# SCH_Lab-bench-Power-Supply_2025-04-24.net
KiCad netlist of a schematic drawn in EasyEDA
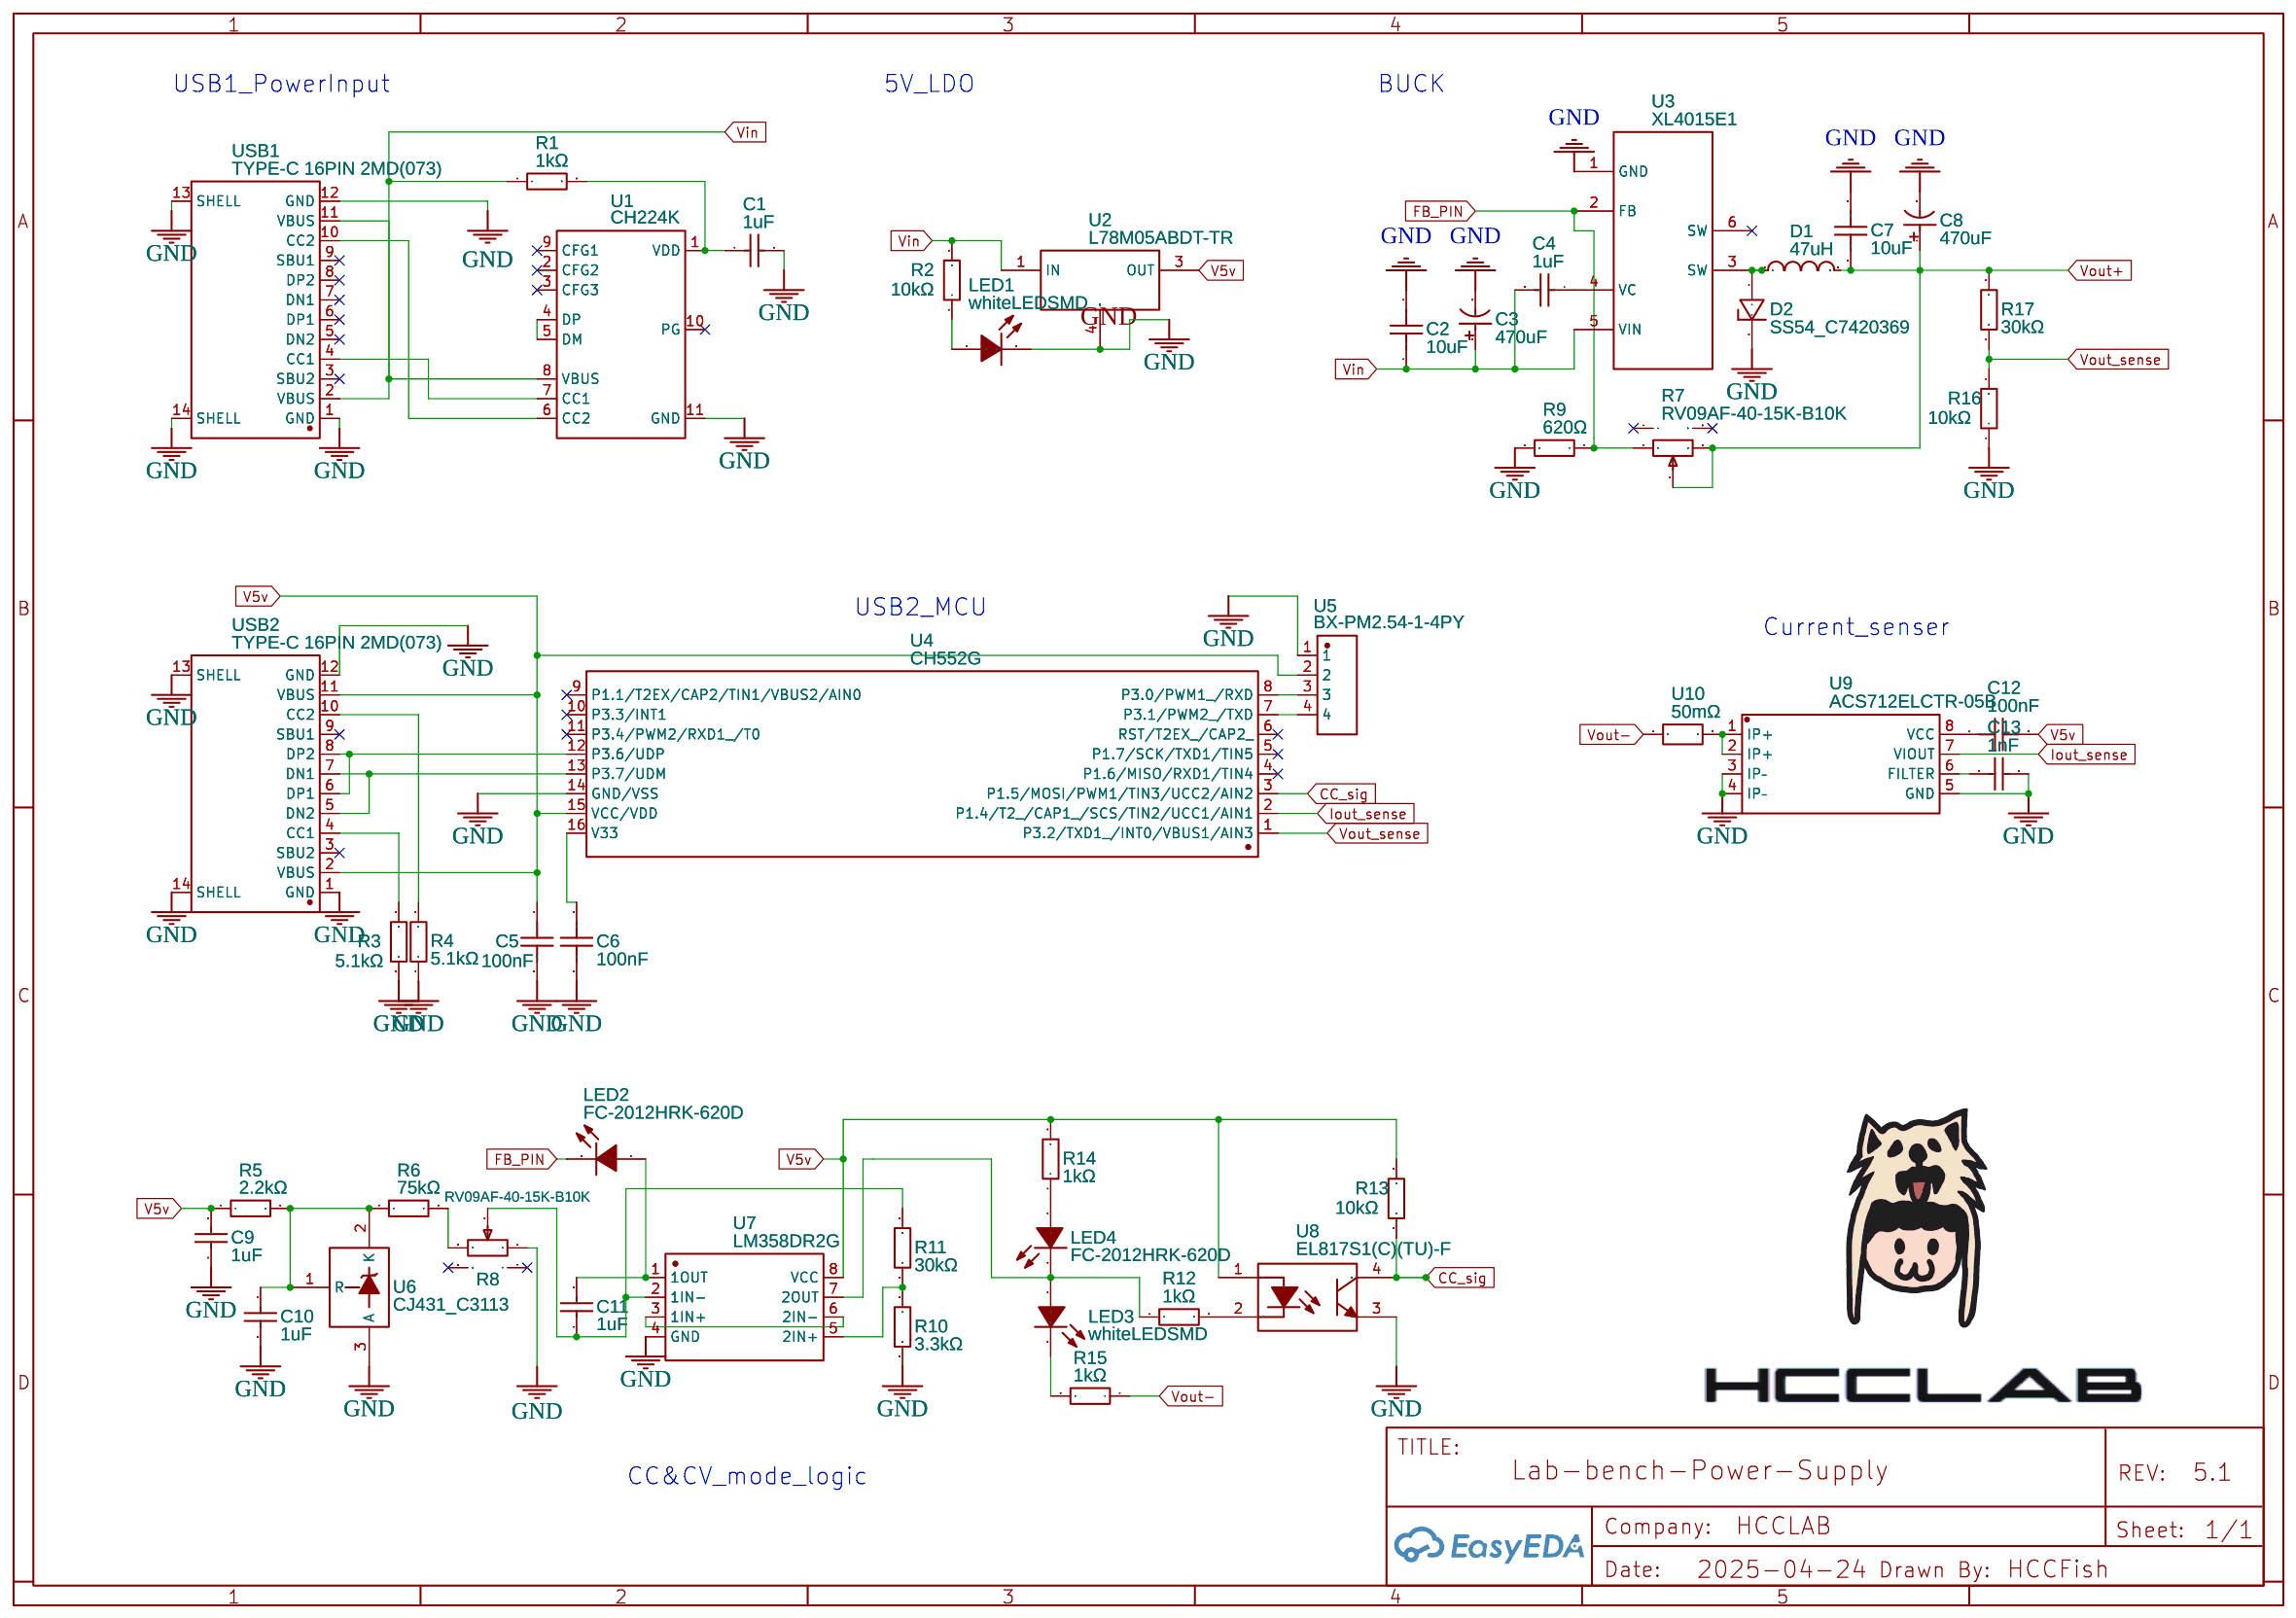
[diagram p0: schematic sheet]

(export (version "E")
  (design (tool "Eeschema 10.0.6"))
  (components
    (comp (ref "C1")
      (value "1uF")
      (fields
        (field (name "Manufacturer Part") "CL21B105KBFNNNE")
        (field (name "Manufacturer") "SAMSUNG(三星)")
      )
      (libsource (lib "") (part "CL21B105KBFNNNE_2"))
    )
    (comp (ref "C2")
      (value "10uF")
      (fields
        (field (name "Manufacturer Part") "CL21A106KAYNNNE")
        (field (name "Manufacturer") "SAMSUNG(三星)")
      )
      (libsource (lib "") (part "CL21A106KAYNNNE"))
    )
    (comp (ref "C3")
      (value "470uF")
      (fields
        (field (name "Manufacturer Part") "KM477M025F12RR0VH2FP0")
        (field (name "Manufacturer") "CX(承兴)")
      )
      (libsource (lib "") (part "470uF 25V 8*12"))
    )
    (comp (ref "C4")
      (value "1uF")
      (fields
        (field (name "Manufacturer Part") "CL21B105KBFNNNE")
        (field (name "Manufacturer") "SAMSUNG(三星)")
      )
      (libsource (lib "") (part "CL21B105KBFNNNE"))
    )
    (comp (ref "C5")
      (value "100nF")
      (fields
        (field (name "Manufacturer Part") "CC0805KRX7R9BB104")
        (field (name "Manufacturer") "YAGEO(国巨)")
      )
      (libsource (lib "") (part "CC0805KRX7R9BB104_2"))
    )
    (comp (ref "C6")
      (value "100nF")
      (fields
        (field (name "Manufacturer Part") "CC0805KRX7R9BB104")
        (field (name "Manufacturer") "YAGEO(国巨)")
      )
      (libsource (lib "") (part "CC0805KRX7R9BB104"))
    )
    (comp (ref "C7")
      (value "10uF")
      (fields
        (field (name "Manufacturer Part") "CL21A106KAYNNNE")
        (field (name "Manufacturer") "SAMSUNG(三星)")
      )
      (libsource (lib "") (part "CL21A106KAYNNNE"))
    )
    (comp (ref "C8")
      (value "470uF")
      (fields
        (field (name "Manufacturer Part") "KM477M025F12RR0VH2FP0")
        (field (name "Manufacturer") "CX(承兴)")
      )
      (libsource (lib "") (part "470uF 25V 8*12"))
    )
    (comp (ref "C9")
      (value "1uF")
      (fields
        (field (name "Manufacturer Part") "CL21B105KBFNNNE")
        (field (name "Manufacturer") "SAMSUNG(三星)")
      )
      (libsource (lib "") (part "CL21B105KBFNNNE_1"))
    )
    (comp (ref "C10")
      (value "1uF")
      (fields
        (field (name "Manufacturer Part") "CL21B105KBFNNNE")
        (field (name "Manufacturer") "SAMSUNG(三星)")
      )
      (libsource (lib "") (part "CL21B105KBFNNNE_1"))
    )
    (comp (ref "C11")
      (value "1uF")
      (fields
        (field (name "Manufacturer Part") "CL21B105KBFNNNE")
        (field (name "Manufacturer") "SAMSUNG(三星)")
      )
      (libsource (lib "") (part "CL21B105KBFNNNE_3"))
    )
    (comp (ref "C12")
      (value "100nF")
      (fields
        (field (name "Manufacturer Part") "CC0805KRX7R9BB104")
        (field (name "Manufacturer") "YAGEO(国巨)")
      )
      (libsource (lib "") (part "CC0805KRX7R9BB104_1"))
    )
    (comp (ref "C13")
      (value "1nF")
      (fields
        (field (name "Manufacturer Part") "CL21B102KBCNNNC")
        (field (name "Manufacturer") "SAMSUNG(三星)")
      )
      (libsource (lib "") (part "CL21B102KBCNNNC"))
    )
    (comp (ref "D1")
      (value "47uH")
      (fields (field (name "Manufacturer Part") "SRP1265A-470M") (field (name "Manufacturer") "BOURNS"))
      (libsource (lib "") (part "SRP1265A-470M"))
    )
    (comp (ref "D2")
      (value "SS54_C7420369")
      (fields (field (name "Manufacturer Part") "SS54") (field (name "Manufacturer") "宏迦橙"))
      (libsource (lib "") (part "SS54_C7420369"))
    )
    (comp (ref "LED1")
      (value "whiteLEDSMD")
      (fields (field (name "Manufacturer Part") "KT-0805W") (field (name "Manufacturer") "KENTO"))
      (libsource (lib "") (part "whiteLEDSMD"))
    )
    (comp (ref "LED2")
      (value "FC-2012HRK-620D")
      (fields (field (name "Manufacturer Part") "NCD0805R1") (field (name "Manufacturer") "国星光电"))
      (libsource (lib "") (part "FC-2012HRK-620D"))
    )
    (comp (ref "LED3")
      (value "whiteLEDSMD")
      (fields (field (name "Manufacturer Part") "KT-0805W") (field (name "Manufacturer") "KENTO"))
      (libsource (lib "") (part "whiteLEDSMD_1"))
    )
    (comp (ref "LED4")
      (value "FC-2012HRK-620D")
      (fields (field (name "Manufacturer Part") "NCD0805R1") (field (name "Manufacturer") "国星光电"))
      (libsource (lib "") (part "FC-2012HRK-620D_1"))
    )
    (comp (ref "R1")
      (value "1kΩ")
      (fields
        (field (name "Manufacturer Part") "0805W8F1001T5E")
        (field (name "Manufacturer") "UNI-ROYAL(厚声)")
      )
      (libsource (lib "") (part "0805W8F1001T5E"))
    )
    (comp (ref "R2")
      (value "10kΩ")
      (fields
        (field (name "Manufacturer Part") "0805W8F1002T5E")
        (field (name "Manufacturer") "UNI-ROYAL(厚声)")
      )
      (libsource (lib "") (part "0805W8F1002T5E"))
    )
    (comp (ref "R3")
      (value "5.1kΩ")
      (fields
        (field (name "Manufacturer Part") "0805W8F5101T5E")
        (field (name "Manufacturer") "UNI-ROYAL(厚声)")
      )
      (libsource (lib "") (part "0805W8F5101T5E"))
    )
    (comp (ref "R4")
      (value "5.1kΩ")
      (fields
        (field (name "Manufacturer Part") "0805W8F5101T5E")
        (field (name "Manufacturer") "UNI-ROYAL(厚声)")
      )
      (libsource (lib "") (part "0805W8F5101T5E"))
    )
    (comp (ref "R5")
      (value "2.2kΩ")
      (fields
        (field (name "Manufacturer Part") "0805W8F2201T5E")
        (field (name "Manufacturer") "UNI-ROYAL(厚声)")
      )
      (libsource (lib "") (part "0805W8F2201T5E"))
    )
    (comp (ref "R6")
      (value "75kΩ")
      (fields
        (field (name "Manufacturer Part") "0805W8F7502T5E")
        (field (name "Manufacturer") "UNI-ROYAL(厚声)")
      )
      (libsource (lib "") (part "0805W8F7502T5E"))
    )
    (comp (ref "R7") (value "RV09AF-40-15K-B10K") (libsource (lib "") (part "RV09AF-40-15K-B10K_1")))
    (comp (ref "R8") (value "RV09AF-40-15K-B10K") (libsource (lib "") (part "RV09AF-40-15K-B10K")))
    (comp (ref "R9")
      (value "620Ω")
      (fields
        (field (name "Manufacturer Part") "0603WAF6200T5E")
        (field (name "Manufacturer") "UNI-ROYAL(厚声)")
      )
      (libsource (lib "") (part "0603WAF6200T5E"))
    )
    (comp (ref "R10")
      (value "3.3kΩ")
      (fields
        (field (name "Manufacturer Part") "0805W8F3301T5E")
        (field (name "Manufacturer") "UNI-ROYAL(厚声)")
      )
      (libsource (lib "") (part "0805W8F3301T5E"))
    )
    (comp (ref "R11")
      (value "30kΩ")
      (fields
        (field (name "Manufacturer Part") "0805W8F3002T5E")
        (field (name "Manufacturer") "UNI-ROYAL(厚声)")
      )
      (libsource (lib "") (part "0805W8F3002T5E"))
    )
    (comp (ref "R12")
      (value "1kΩ")
      (fields
        (field (name "Manufacturer Part") "0805W8F1001T5E")
        (field (name "Manufacturer") "UNI-ROYAL(厚声)")
      )
      (libsource (lib "") (part "0805W8F1001T5E"))
    )
    (comp (ref "R13")
      (value "10kΩ")
      (fields
        (field (name "Manufacturer Part") "0805W8F1002T5E")
        (field (name "Manufacturer") "UNI-ROYAL(厚声)")
      )
      (libsource (lib "") (part "0805W8F1002T5E"))
    )
    (comp (ref "R14")
      (value "1kΩ")
      (fields
        (field (name "Manufacturer Part") "0805W8F1001T5E")
        (field (name "Manufacturer") "UNI-ROYAL(厚声)")
      )
      (libsource (lib "") (part "0805W8F1001T5E_1"))
    )
    (comp (ref "R15")
      (value "1kΩ")
      (fields
        (field (name "Manufacturer Part") "0805W8F1001T5E")
        (field (name "Manufacturer") "UNI-ROYAL(厚声)")
      )
      (libsource (lib "") (part "0805W8F1001T5E_2"))
    )
    (comp (ref "R16")
      (value "10kΩ")
      (fields
        (field (name "Manufacturer Part") "0805W8F1002T5E")
        (field (name "Manufacturer") "UNI-ROYAL(厚声)")
      )
      (libsource (lib "") (part "0805W8F1002T5E"))
    )
    (comp (ref "R17")
      (value "30kΩ")
      (fields
        (field (name "Manufacturer Part") "0805W8F3002T5E")
        (field (name "Manufacturer") "UNI-ROYAL(厚声)")
      )
      (libsource (lib "") (part "0805W8F3002T5E"))
    )
    (comp (ref "U1")
      (value "CH224K")
      (fields (field (name "Manufacturer") "WCH(南京沁恒)"))
      (libsource (lib "") (part "CH224K"))
    )
    (comp (ref "U2")
      (value "L78M05ABDT-TR")
      (fields (field (name "Manufacturer") "ST(意法半导体)"))
      (libsource (lib "") (part "L78M05ABDT-TR"))
    )
    (comp (ref "U3")
      (value "XL4015E1")
      (fields (field (name "Manufacturer") "XLSEMI(芯龙)"))
      (libsource (lib "") (part "XL4015E1"))
    )
    (comp (ref "U4")
      (value "CH552G")
      (fields (field (name "Manufacturer") "WCH(南京沁恒)"))
      (libsource (lib "") (part "CH552G"))
    )
    (comp (ref "U5")
      (value "BX-PM2.54-1-4PY")
      (fields (field (name "Manufacturer") "Bossie(博锡)"))
      (libsource (lib "") (part "BX-PM2.54-1-4PY"))
    )
    (comp (ref "U6")
      (value "CJ431_C3113")
      (fields (field (name "Manufacturer Part") "CJ431") (field (name "Manufacturer") "CJ(江苏长电/长晶)"))
      (libsource (lib "") (part "CJ431_C3113"))
    )
    (comp (ref "U7")
      (value "LM358DR2G")
      (fields (field (name "Manufacturer") "onsemi(安森美)"))
      (libsource (lib "") (part "LM358DR2G"))
    )
    (comp (ref "U8")
      (value "EL817S1(C)(TU)-F")
      (fields (field (name "Manufacturer") "EVERLIGHT(亿光)"))
      (libsource (lib "") (part "EL817S1(C)(TU)-F"))
    )
    (comp (ref "U9")
      (value "ACS712ELCTR-05B")
      (fields (field (name "Manufacturer") "ALLEGRO(美国埃戈罗)"))
      (libsource (lib "") (part "ACS712ELCTR-05B"))
    )
    (comp (ref "U10")
      (value "50mΩ")
      (fields
        (field (name "Manufacturer Part") "HoYLR2512-3W-50mR-1%")
        (field (name "Manufacturer") "Milliohm(毫欧)")
      )
      (libsource (lib "") (part "HOYLR2512-3W-50MR-1%"))
    )
    (comp (ref "USB1")
      (value "TYPE-C 16PIN 2MD(073)")
      (fields (field (name "Manufacturer") "SHOU HAN(首韩)"))
      (libsource (lib "") (part "TYPE-C 16PIN 2MD(073)"))
    )
    (comp (ref "USB2")
      (value "TYPE-C 16PIN 2MD(073)")
      (fields (field (name "Manufacturer") "SHOU HAN(首韩)"))
      (libsource (lib "") (part "TYPE-C 16PIN 2MD(073)"))
    )
  )
  (nets
    (net (code "1") (name "CC_sig") (class "Default")
      (node (ref "R13") (pin "1") (pinfunction "1_1") (pintype "input"))
      (node (ref "U4") (pin "3") (pinfunction "P1.5/MOSI/PWM1/TIN3/UCC2/AIN2_3") (pintype "unspecified"))
      (node (ref "U8") (pin "4") (pinfunction "COL_4") (pintype "unspecified"))
    )
    (net (code "2") (name "FB_PIN") (class "Default")
      (node (ref "LED2") (pin "2") (pinfunction "-_2") (pintype "unspecified"))
      (node (ref "R7") (pin "1") (pinfunction "1_1") (pintype "input"))
      (node (ref "R9") (pin "1") (pinfunction "1_1") (pintype "input"))
      (node (ref "U3") (pin "2") (pinfunction "FB_2") (pintype "unspecified"))
    )
    (net (code "3") (name "GND") (class "Default")
      (node (ref "C1") (pin "2") (pinfunction "2_2") (pintype "input"))
      (node (ref "C10") (pin "2") (pinfunction "2_2") (pintype "input"))
      (node (ref "C13") (pin "2") (pinfunction "2_2") (pintype "input"))
      (node (ref "C2") (pin "2") (pinfunction "2_2") (pintype "unspecified"))
      (node (ref "C3") (pin "2") (pinfunction "2_2") (pintype "input"))
      (node (ref "C5") (pin "2") (pinfunction "2_2") (pintype "unspecified"))
      (node (ref "C6") (pin "1") (pinfunction "1_1") (pintype "unspecified"))
      (node (ref "C7") (pin "2") (pinfunction "2_2") (pintype "unspecified"))
      (node (ref "C8") (pin "2") (pinfunction "2_2") (pintype "input"))
      (node (ref "C9") (pin "2") (pinfunction "2_2") (pintype "input"))
      (node (ref "D2") (pin "2") (pinfunction "K_2") (pintype "unspecified"))
      (node (ref "LED1") (pin "2") (pinfunction "K_2") (pintype "unspecified"))
      (node (ref "R10") (pin "2") (pinfunction "2_2") (pintype "input"))
      (node (ref "R16") (pin "1") (pinfunction "1_1") (pintype "input"))
      (node (ref "R3") (pin "1") (pinfunction "1_1") (pintype "input"))
      (node (ref "R4") (pin "1") (pinfunction "1_1") (pintype "input"))
      (node (ref "R8") (pin "1") (pinfunction "1_1") (pintype "input"))
      (node (ref "R9") (pin "2") (pinfunction "2_2") (pintype "input"))
      (node (ref "U1") (pin "11") (pinfunction "GND_11") (pintype "unspecified"))
      (node (ref "U2") (pin "4") (pinfunction "GND_4") (pintype "passive"))
      (node (ref "U3") (pin "1") (pinfunction "GND_1") (pintype "unspecified"))
      (node (ref "U4") (pin "14") (pinfunction "GND/VSS_14") (pintype "unspecified"))
      (node (ref "U5") (pin "1") (pinfunction "1_1") (pintype "unspecified"))
      (node (ref "U6") (pin "3") (pinfunction "A_3") (pintype "unspecified"))
      (node (ref "U7") (pin "4") (pinfunction "GND_4") (pintype "unspecified"))
      (node (ref "U8") (pin "3") (pinfunction "EM_3") (pintype "unspecified"))
      (node (ref "U9") (pin "3") (pinfunction "IP–_3") (pintype "unspecified"))
      (node (ref "U9") (pin "4") (pinfunction "IP–_4") (pintype "unspecified"))
      (node (ref "U9") (pin "5") (pinfunction "GND_5") (pintype "unspecified"))
      (node (ref "USB1") (pin "1") (pinfunction "GND_1") (pintype "unspecified"))
      (node (ref "USB1") (pin "12") (pinfunction "GND_12") (pintype "unspecified"))
      (node (ref "USB1") (pin "13") (pinfunction "SHELL_13") (pintype "unspecified"))
      (node (ref "USB1") (pin "14") (pinfunction "SHELL_14") (pintype "unspecified"))
      (node (ref "USB2") (pin "1") (pinfunction "GND_1") (pintype "unspecified"))
      (node (ref "USB2") (pin "12") (pinfunction "GND_12") (pintype "unspecified"))
      (node (ref "USB2") (pin "13") (pinfunction "SHELL_13") (pintype "unspecified"))
      (node (ref "USB2") (pin "14") (pinfunction "SHELL_14") (pintype "unspecified"))
    )
    (net (code "4") (name "Iout_sense") (class "Default")
      (node (ref "U4") (pin "2") (pinfunction "P1.4/T2_/CAP1_/SCS/TIN2/UCC1/AIN1_2") (pintype "unspecified"))
      (node (ref "U9") (pin "7") (pinfunction "VIOUT_7") (pintype "unspecified"))
    )
    (net (code "5") (name "Net-(D2-A)") (class "Default")
      (node (ref "D1") (pin "1") (pinfunction "1_1") (pintype "unspecified"))
      (node (ref "D2") (pin "1") (pinfunction "A_1") (pintype "unspecified"))
      (node (ref "U3") (pin "3") (pinfunction "SW_3") (pintype "unspecified"))
    )
    (net (code "6") (name "Net-(LED1-A)") (class "Default")
      (node (ref "LED1") (pin "1") (pinfunction "A_1") (pintype "unspecified"))
      (node (ref "R2") (pin "1") (pinfunction "1_1") (pintype "input"))
    )
    (net (code "7") (name "Net-(LED2-+)") (class "Default")
      (node (ref "C11") (pin "2") (pinfunction "2_2") (pintype "input"))
      (node (ref "LED2") (pin "1") (pinfunction "+_1") (pintype "unspecified"))
      (node (ref "U7") (pin "1") (pinfunction "1OUT_1") (pintype "unspecified"))
    )
    (net (code "8") (name "Net-(LED3-A)") (class "Default")
      (node (ref "LED3") (pin "1") (pinfunction "A_1") (pintype "unspecified"))
      (node (ref "LED4") (pin "2") (pinfunction "-_2") (pintype "unspecified"))
      (node (ref "R12") (pin "1") (pinfunction "1_1") (pintype "input"))
      (node (ref "U7") (pin "7") (pinfunction "2OUT_7") (pintype "unspecified"))
    )
    (net (code "9") (name "Net-(LED3-K)") (class "Default")
      (node (ref "LED3") (pin "2") (pinfunction "K_2") (pintype "unspecified"))
      (node (ref "R15") (pin "2") (pinfunction "2_2") (pintype "input"))
    )
    (net (code "10") (name "Net-(LED4-+)") (class "Default")
      (node (ref "LED4") (pin "1") (pinfunction "+_1") (pintype "unspecified"))
      (node (ref "R14") (pin "1") (pinfunction "1_1") (pintype "input"))
    )
    (net (code "11") (name "Net-(R6-Pad2)") (class "Default")
      (node (ref "R6") (pin "2") (pinfunction "2_2") (pintype "input"))
      (node (ref "R8") (pin "3") (pinfunction "3_3") (pintype "input"))
    )
    (net (code "12") (name "Net-(U1-CC1)") (class "Default")
      (node (ref "U1") (pin "7") (pinfunction "CC1_7") (pintype "unspecified"))
      (node (ref "USB1") (pin "4") (pinfunction "CC1_4") (pintype "unspecified"))
    )
    (net (code "13") (name "Net-(U1-CC2)") (class "Default")
      (node (ref "U1") (pin "6") (pinfunction "CC2_6") (pintype "unspecified"))
      (node (ref "USB1") (pin "10") (pinfunction "CC2_10") (pintype "unspecified"))
    )
    (net (code "14") (name "Net-(U1-DM)") (class "Default")
      (node (ref "U1") (pin "4") (pinfunction "DP_4") (pintype "unspecified"))
      (node (ref "U1") (pin "5") (pinfunction "DM_5") (pintype "unspecified"))
    )
    (net (code "15") (name "Net-(U1-VDD)") (class "Default")
      (node (ref "C1") (pin "1") (pinfunction "1_1") (pintype "input"))
      (node (ref "R1") (pin "2") (pinfunction "2_2") (pintype "input"))
      (node (ref "U1") (pin "1") (pinfunction "VDD_1") (pintype "unspecified"))
    )
    (net (code "16") (name "Net-(U3-VC)") (class "Default")
      (node (ref "C4") (pin "1") (pinfunction "1_1") (pintype "input"))
      (node (ref "U3") (pin "4") (pinfunction "VC_4") (pintype "unspecified"))
    )
    (net (code "17") (name "Net-(U4-P3.0{slash}PWM1_{slash}RXD)") (class "Default")
      (node (ref "U4") (pin "8") (pinfunction "P3.0/PWM1_/RXD_8") (pintype "unspecified"))
      (node (ref "U5") (pin "3") (pinfunction "3_3") (pintype "unspecified"))
    )
    (net (code "18") (name "Net-(U4-P3.1{slash}PWM2_{slash}TXD)") (class "Default")
      (node (ref "U4") (pin "7") (pinfunction "P3.1/PWM2_/TXD_7") (pintype "unspecified"))
      (node (ref "U5") (pin "4") (pinfunction "4_4") (pintype "unspecified"))
    )
    (net (code "19") (name "Net-(U4-P3.6{slash}UDP)") (class "Default")
      (node (ref "U4") (pin "12") (pinfunction "P3.6/UDP_12") (pintype "unspecified"))
      (node (ref "USB2") (pin "6") (pinfunction "DP1_6") (pintype "unspecified"))
      (node (ref "USB2") (pin "8") (pinfunction "DP2_8") (pintype "unspecified"))
    )
    (net (code "20") (name "Net-(U4-P3.7{slash}UDM)") (class "Default")
      (node (ref "U4") (pin "13") (pinfunction "P3.7/UDM_13") (pintype "unspecified"))
      (node (ref "USB2") (pin "5") (pinfunction "DN2_5") (pintype "unspecified"))
      (node (ref "USB2") (pin "7") (pinfunction "DN1_7") (pintype "unspecified"))
    )
    (net (code "21") (name "Net-(U4-V33)") (class "Default")
      (node (ref "C6") (pin "2") (pinfunction "2_2") (pintype "unspecified"))
      (node (ref "U4") (pin "16") (pinfunction "V33_16") (pintype "unspecified"))
    )
    (net (code "22") (name "Net-(U6-K)") (class "Default")
      (node (ref "C10") (pin "1") (pinfunction "1_1") (pintype "input"))
      (node (ref "R5") (pin "2") (pinfunction "2_2") (pintype "input"))
      (node (ref "R6") (pin "1") (pinfunction "1_1") (pintype "input"))
      (node (ref "U6") (pin "1") (pinfunction "R_1") (pintype "unspecified"))
      (node (ref "U6") (pin "2") (pinfunction "K_2") (pintype "unspecified"))
    )
    (net (code "23") (name "Net-(U7-1IN+)") (class "Default")
      (node (ref "U7") (pin "3") (pinfunction "1IN+_3") (pintype "unspecified"))
      (node (ref "U7") (pin "6") (pinfunction "2IN-_6") (pintype "unspecified"))
    )
    (net (code "24") (name "Net-(U7-1IN-)") (class "Default")
      (node (ref "C11") (pin "1") (pinfunction "1_1") (pintype "input"))
      (node (ref "R11") (pin "2") (pinfunction "2_2") (pintype "input"))
      (node (ref "R8") (pin "2") (pinfunction "2_2") (pintype "input"))
      (node (ref "U7") (pin "2") (pinfunction "1IN-_2") (pintype "unspecified"))
    )
    (net (code "25") (name "Net-(U7-2IN+)") (class "Default")
      (node (ref "R10") (pin "1") (pinfunction "1_1") (pintype "input"))
      (node (ref "R11") (pin "1") (pinfunction "1_1") (pintype "input"))
      (node (ref "U7") (pin "5") (pinfunction "2IN+_5") (pintype "unspecified"))
    )
    (net (code "26") (name "Net-(U8-CAT)") (class "Default")
      (node (ref "R12") (pin "2") (pinfunction "2_2") (pintype "input"))
      (node (ref "U8") (pin "2") (pinfunction "CAT_2") (pintype "unspecified"))
    )
    (net (code "27") (name "Net-(U9-FILTER)") (class "Default")
      (node (ref "C13") (pin "1") (pinfunction "1_1") (pintype "input"))
      (node (ref "U9") (pin "6") (pinfunction "FILTER_6") (pintype "unspecified"))
    )
    (net (code "28") (name "Net-(U9-VCC)") (class "Default")
      (node (ref "C12") (pin "1") (pinfunction "1_1") (pintype "unspecified"))
      (node (ref "U9") (pin "8") (pinfunction "VCC_8") (pintype "unspecified"))
    )
    (net (code "29") (name "Net-(U10-Pad2)") (class "Default")
      (node (ref "U10") (pin "2") (pinfunction "2_2") (pintype "unspecified"))
      (node (ref "U9") (pin "1") (pinfunction "IP+_1") (pintype "unspecified"))
      (node (ref "U9") (pin "2") (pinfunction "IP+_2") (pintype "unspecified"))
    )
    (net (code "30") (name "Net-(USB2-CC1)") (class "Default")
      (node (ref "R3") (pin "2") (pinfunction "2_2") (pintype "input"))
      (node (ref "USB2") (pin "4") (pinfunction "CC1_4") (pintype "unspecified"))
    )
    (net (code "31") (name "Net-(USB2-CC2)") (class "Default")
      (node (ref "R4") (pin "2") (pinfunction "2_2") (pintype "input"))
      (node (ref "USB2") (pin "10") (pinfunction "CC2_10") (pintype "unspecified"))
    )
    (net (code "32") (name "V5v") (class "Default")
      (node (ref "C12") (pin "2") (pinfunction "2_2") (pintype "unspecified"))
      (node (ref "C5") (pin "1") (pinfunction "1_1") (pintype "unspecified"))
      (node (ref "C9") (pin "1") (pinfunction "1_1") (pintype "input"))
      (node (ref "R13") (pin "2") (pinfunction "2_2") (pintype "input"))
      (node (ref "R14") (pin "2") (pinfunction "2_2") (pintype "input"))
      (node (ref "R5") (pin "1") (pinfunction "1_1") (pintype "input"))
      (node (ref "U2") (pin "3") (pinfunction "OUT_3") (pintype "passive"))
      (node (ref "U4") (pin "15") (pinfunction "VCC/VDD_15") (pintype "unspecified"))
      (node (ref "U5") (pin "2") (pinfunction "2_2") (pintype "unspecified"))
      (node (ref "U7") (pin "8") (pinfunction "VCC_8") (pintype "unspecified"))
      (node (ref "U8") (pin "1") (pinfunction "AN_1") (pintype "unspecified"))
      (node (ref "USB2") (pin "11") (pinfunction "VBUS_11") (pintype "unspecified"))
      (node (ref "USB2") (pin "2") (pinfunction "VBUS_2") (pintype "unspecified"))
    )
    (net (code "33") (name "Vin") (class "Default")
      (node (ref "C2") (pin "1") (pinfunction "1_1") (pintype "unspecified"))
      (node (ref "C3") (pin "1") (pinfunction "1_1") (pintype "input"))
      (node (ref "C4") (pin "2") (pinfunction "2_2") (pintype "input"))
      (node (ref "R1") (pin "1") (pinfunction "1_1") (pintype "input"))
      (node (ref "R2") (pin "2") (pinfunction "2_2") (pintype "input"))
      (node (ref "U1") (pin "8") (pinfunction "VBUS_8") (pintype "unspecified"))
      (node (ref "U2") (pin "1") (pinfunction "IN_1") (pintype "passive"))
      (node (ref "U3") (pin "5") (pinfunction "VIN_5") (pintype "unspecified"))
      (node (ref "USB1") (pin "11") (pinfunction "VBUS_11") (pintype "unspecified"))
      (node (ref "USB1") (pin "2") (pinfunction "VBUS_2") (pintype "unspecified"))
    )
    (net (code "34") (name "Vout+") (class "Default")
      (node (ref "C7") (pin "1") (pinfunction "1_1") (pintype "unspecified"))
      (node (ref "C8") (pin "1") (pinfunction "1_1") (pintype "input"))
      (node (ref "D1") (pin "2") (pinfunction "2_2") (pintype "unspecified"))
      (node (ref "R17") (pin "2") (pinfunction "2_2") (pintype "input"))
      (node (ref "R7") (pin "2") (pinfunction "2_2") (pintype "input"))
      (node (ref "R7") (pin "3") (pinfunction "3_3") (pintype "input"))
    )
    (net (code "35") (name "Vout-") (class "Default")
      (node (ref "R15") (pin "1") (pinfunction "1_1") (pintype "input"))
      (node (ref "U10") (pin "1") (pinfunction "1_1") (pintype "unspecified"))
    )
    (net (code "36") (name "Vout_sense") (class "Default")
      (node (ref "R16") (pin "2") (pinfunction "2_2") (pintype "input"))
      (node (ref "R17") (pin "1") (pinfunction "1_1") (pintype "input"))
      (node (ref "U4") (pin "1") (pinfunction "P3.2/TXD1_/INT0/VBUS1/AIN3_1") (pintype "unspecified"))
    )
    (net (code "37") (name "unconnected-(R7-Pad4)") (class "Default")
      (node (ref "R7") (pin "4") (pinfunction "4_4") (pintype "input+no_connect"))
    )
    (net (code "38") (name "unconnected-(R7-Pad5)") (class "Default")
      (node (ref "R7") (pin "5") (pinfunction "5_5") (pintype "input+no_connect"))
    )
    (net (code "39") (name "unconnected-(R8-Pad4)") (class "Default")
      (node (ref "R8") (pin "4") (pinfunction "4_4") (pintype "input+no_connect"))
    )
    (net (code "40") (name "unconnected-(R8-Pad5)") (class "Default")
      (node (ref "R8") (pin "5") (pinfunction "5_5") (pintype "input+no_connect"))
    )
    (net (code "41") (name "unconnected-(U1-CFG1-Pad9)") (class "Default")
      (node (ref "U1") (pin "9") (pinfunction "CFG1_9") (pintype "unspecified+no_connect"))
    )
    (net (code "42") (name "unconnected-(U1-CFG2-Pad2)") (class "Default")
      (node (ref "U1") (pin "2") (pinfunction "CFG2_2") (pintype "unspecified+no_connect"))
    )
    (net (code "43") (name "unconnected-(U1-CFG3-Pad3)") (class "Default")
      (node (ref "U1") (pin "3") (pinfunction "CFG3_3") (pintype "unspecified+no_connect"))
    )
    (net (code "44") (name "unconnected-(U1-PG-Pad10)") (class "Default")
      (node (ref "U1") (pin "10") (pinfunction "PG_10") (pintype "unspecified+no_connect"))
    )
    (net (code "45") (name "unconnected-(U3-SW-Pad6)") (class "Default")
      (node (ref "U3") (pin "6") (pinfunction "SW_6") (pintype "unspecified+no_connect"))
    )
    (net (code "46") (name "unconnected-(U4-P1.1{slash}T2EX{slash}CAP2{slash}TIN1{slash}VBUS2{slash}AIN0-Pad9)") (class "Default")
      (node (ref "U4") (pin "9") (pinfunction "P1.1/T2EX/CAP2/TIN1/VBUS2/AIN0_9") (pintype "unspecified+no_connect"))
    )
    (net (code "47") (name "unconnected-(U4-P1.6{slash}MISO{slash}RXD1{slash}TIN4-Pad4)") (class "Default")
      (node (ref "U4") (pin "4") (pinfunction "P1.6/MISO/RXD1/TIN4_4") (pintype "unspecified+no_connect"))
    )
    (net (code "48") (name "unconnected-(U4-P1.7{slash}SCK{slash}TXD1{slash}TIN5-Pad5)") (class "Default")
      (node (ref "U4") (pin "5") (pinfunction "P1.7/SCK/TXD1/TIN5_5") (pintype "unspecified+no_connect"))
    )
    (net (code "49") (name "unconnected-(U4-P3.3{slash}INT1-Pad10)") (class "Default")
      (node (ref "U4") (pin "10") (pinfunction "P3.3/INT1_10") (pintype "unspecified+no_connect"))
    )
    (net (code "50") (name "unconnected-(U4-P3.4{slash}PWM2{slash}RXD1_{slash}T0-Pad11)") (class "Default")
      (node (ref "U4") (pin "11") (pinfunction "P3.4/PWM2/RXD1_/T0_11") (pintype "unspecified+no_connect"))
    )
    (net (code "51") (name "unconnected-(U4-RST{slash}T2EX_{slash}CAP2_-Pad6)") (class "Default")
      (node (ref "U4") (pin "6") (pinfunction "RST/T2EX_/CAP2__6") (pintype "unspecified+no_connect"))
    )
    (net (code "52") (name "unconnected-(USB1-DN1-Pad7)") (class "Default")
      (node (ref "USB1") (pin "7") (pinfunction "DN1_7") (pintype "unspecified+no_connect"))
    )
    (net (code "53") (name "unconnected-(USB1-DN2-Pad5)") (class "Default")
      (node (ref "USB1") (pin "5") (pinfunction "DN2_5") (pintype "unspecified+no_connect"))
    )
    (net (code "54") (name "unconnected-(USB1-DP1-Pad6)") (class "Default")
      (node (ref "USB1") (pin "6") (pinfunction "DP1_6") (pintype "unspecified+no_connect"))
    )
    (net (code "55") (name "unconnected-(USB1-DP2-Pad8)") (class "Default")
      (node (ref "USB1") (pin "8") (pinfunction "DP2_8") (pintype "unspecified+no_connect"))
    )
    (net (code "56") (name "unconnected-(USB1-SBU1-Pad9)") (class "Default")
      (node (ref "USB1") (pin "9") (pinfunction "SBU1_9") (pintype "unspecified+no_connect"))
    )
    (net (code "57") (name "unconnected-(USB1-SBU2-Pad3)") (class "Default")
      (node (ref "USB1") (pin "3") (pinfunction "SBU2_3") (pintype "unspecified+no_connect"))
    )
    (net (code "58") (name "unconnected-(USB2-SBU1-Pad9)") (class "Default")
      (node (ref "USB2") (pin "9") (pinfunction "SBU1_9") (pintype "unspecified+no_connect"))
    )
    (net (code "59") (name "unconnected-(USB2-SBU2-Pad3)") (class "Default")
      (node (ref "USB2") (pin "3") (pinfunction "SBU2_3") (pintype "unspecified+no_connect"))
    )
  )
)
